# 17_-_MECH.net
KiCad netlist of a schematic drawn in Altium Designer
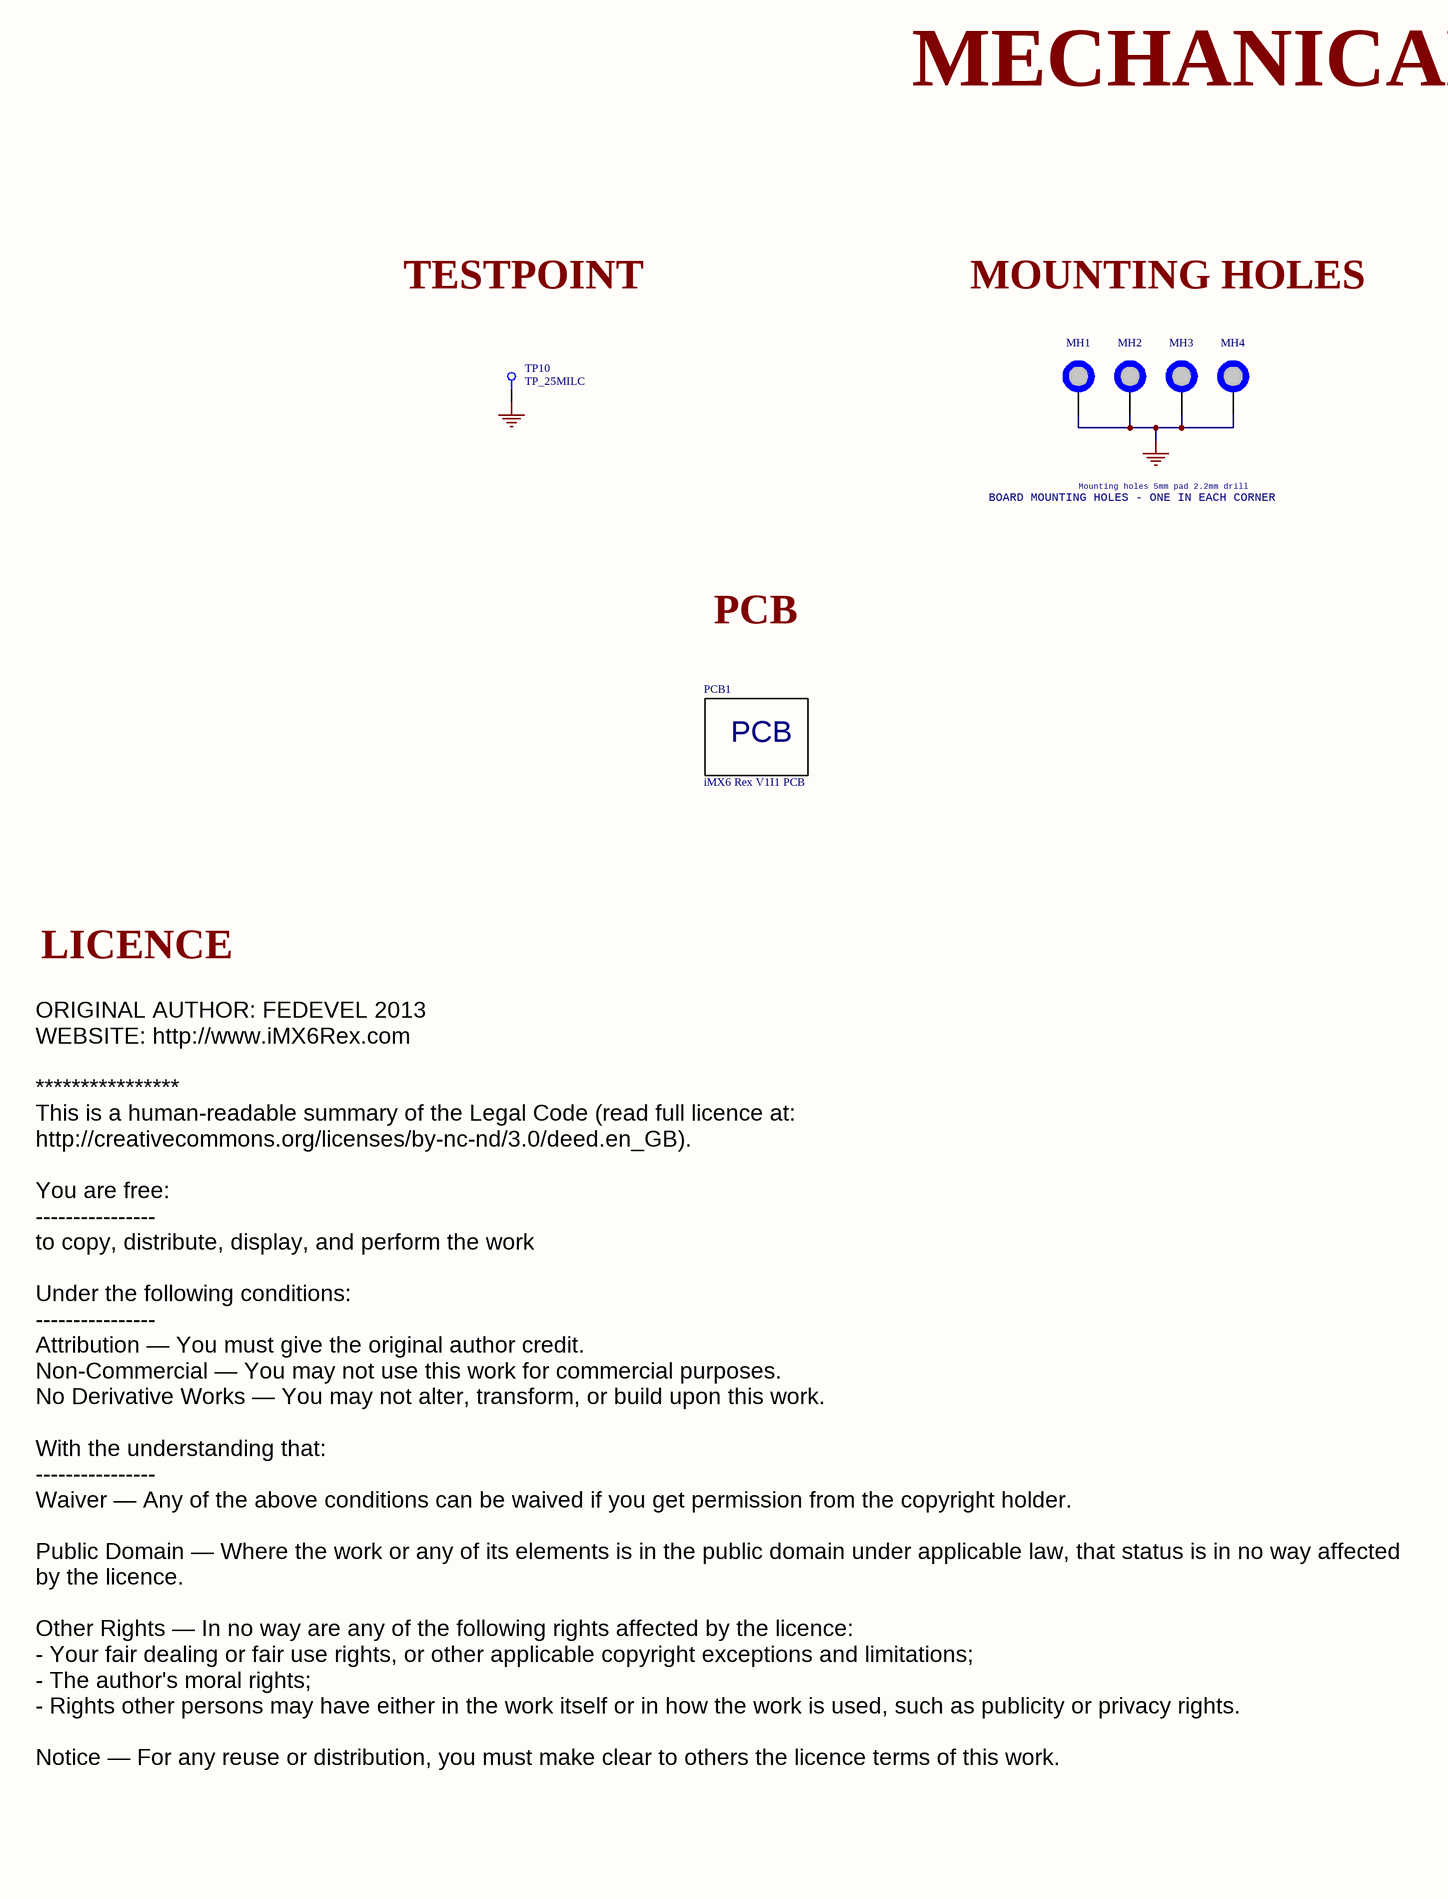
[diagram p0: [17] - MECH.SchDoc, left]
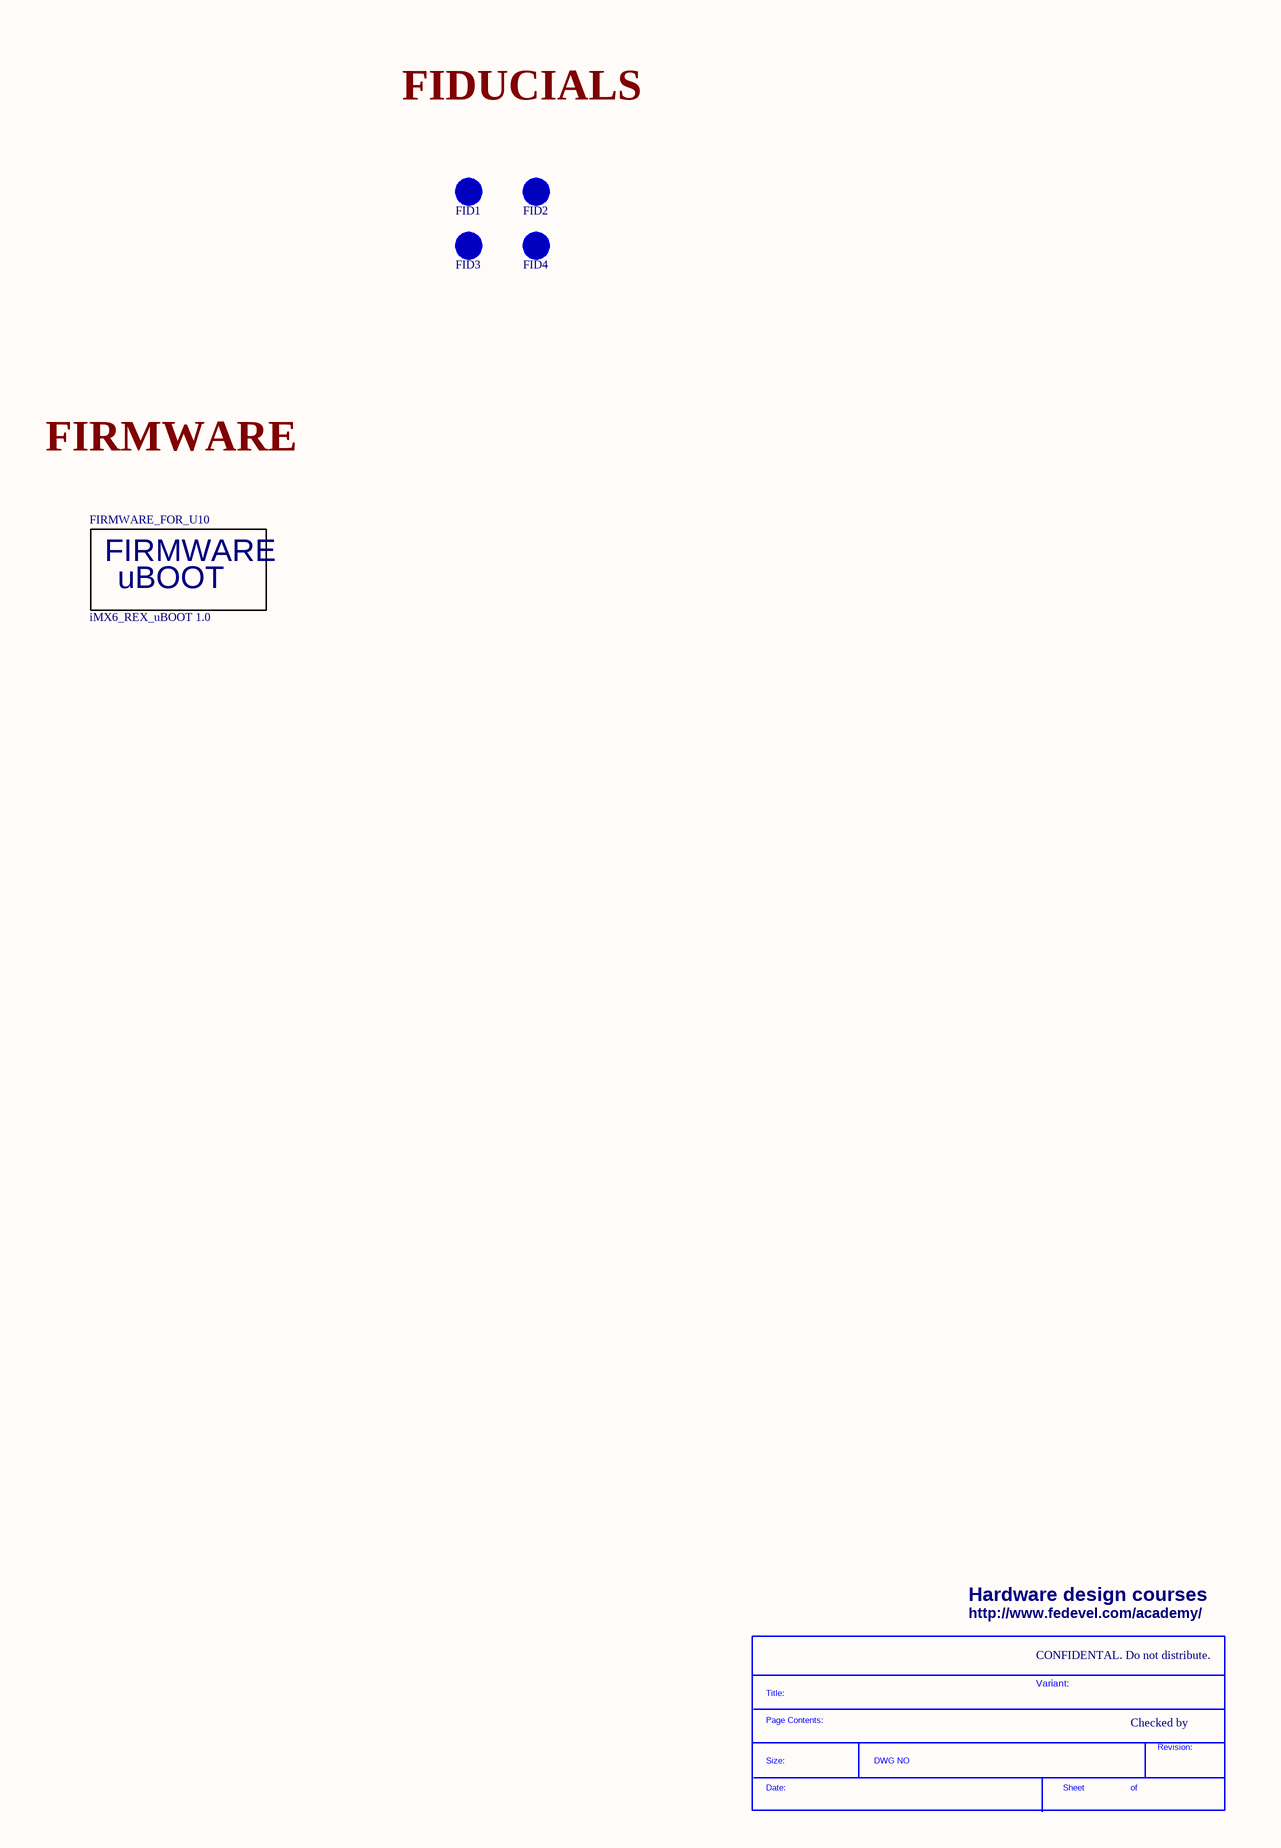
[diagram p1: [17] - MECH.SchDoc, right]

(export (version "E")
  (design (tool "Eeschema 10.0.6"))
  (components
    (comp (ref "FID1")
      (value "FID_1MM_SMALL")
      (footprint "FID_40X52D")
      (description "Fiducial 40mil Diameter, 52mil Mask")
      (libsource (lib "Integrated_Library_RF_FEB_2012") (part "FID_1MM_SMALL"))
    )
    (comp (ref "FID2")
      (value "FID_1MM_SMALL")
      (footprint "FID_40X52D")
      (description "Fiducial 40mil Diameter, 52mil Mask")
      (libsource (lib "Integrated_Library_RF_FEB_2012") (part "FID_1MM_SMALL"))
    )
    (comp (ref "FID3")
      (value "FID_1MM_SMALL")
      (footprint "FID_40X52D")
      (description "Fiducial 40mil Diameter, 52mil Mask")
      (libsource (lib "Integrated_Library_RF_FEB_2012") (part "FID_1MM_SMALL"))
    )
    (comp (ref "FID4")
      (value "FID_1MM_SMALL")
      (footprint "FID_40X52D")
      (description "Fiducial 40mil Diameter, 52mil Mask")
      (libsource (lib "Integrated_Library_RF_FEB_2012") (part "FID_1MM_SMALL"))
    )
    (comp (ref "FIRMWARE_FOR_U10")
      (value "iMX6_REX_uBOOT 1.0")
      (fields (field (name ".CREATOR") "MM"))
      (libsource (lib "Schlib_RF") (part "FIRMWARE_iMX6_Rex_uBOOT 1.0"))
    )
    (comp (ref "MH1")
      (value "MH_5MMC_2.2MMD")
      (footprint "MH_5MMD_2.2MMD")
      (description "Mounting Hole 5mm Diameter, 2.2mm Drill")
      (libsource (lib "Integrated_Library_RF_FEB_2012") (part "MH_5MMC_2.2MMD"))
    )
    (comp (ref "MH2")
      (value "MH_5MMC_2.2MMD")
      (footprint "MH_5MMD_2.2MMD")
      (description "Mounting Hole 5mm Diameter, 2.2mm Drill")
      (libsource (lib "Integrated_Library_RF_FEB_2012") (part "MH_5MMC_2.2MMD"))
    )
    (comp (ref "MH3")
      (value "MH_5MMC_2.2MMD")
      (footprint "MH_5MMD_2.2MMD")
      (description "Mounting Hole 5mm Diameter, 2.2mm Drill")
      (libsource (lib "Integrated_Library_RF_FEB_2012") (part "MH_5MMC_2.2MMD"))
    )
    (comp (ref "MH4")
      (value "MH_5MMC_2.2MMD")
      (footprint "MH_5MMD_2.2MMD")
      (description "Mounting Hole 5mm Diameter, 2.2mm Drill")
      (libsource (lib "Integrated_Library_RF_FEB_2012") (part "MH_5MMC_2.2MMD"))
    )
    (comp (ref "PCB1")
      (value "iMX6 Rex V1I1 PCB")
      (description "Printed Circuit Board")
      (fields (field (name ".CREATOR") "MM"))
      (libsource (lib "Integrated_Library_RF_FEB_2012") (part "PCB_iMX6_REX_V1I1"))
    )
    (comp (ref "TP10")
      (value "TP_25MILC")
      (footprint "TP_25C")
      (description "Test Point 25mil")
      (libsource (lib "Integrated_Library_RF_FEB_2012") (part "TP_25MILC"))
    )
  )
  (nets
    (net (code "1") (name "GND") (class "Default")
      (node (ref "MH1") (pin "1") (pinfunction "1_1") (pintype "passive"))
      (node (ref "MH2") (pin "1") (pinfunction "1_1") (pintype "passive"))
      (node (ref "MH3") (pin "1") (pinfunction "1_1") (pintype "passive"))
      (node (ref "MH4") (pin "1") (pinfunction "1_1") (pintype "passive"))
      (node (ref "TP10") (pin "1") (pinfunction "1_1") (pintype "passive"))
    )
  )
)
